# main.net
KiCad netlist of a schematic drawn in Altium Designer
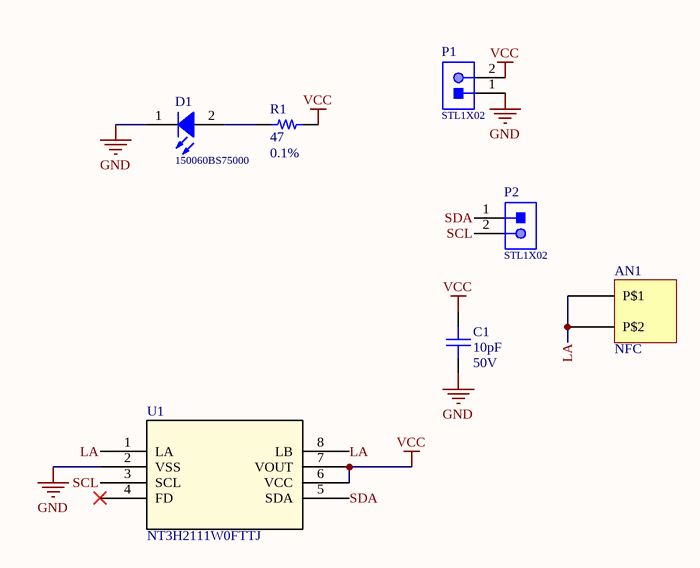
[diagram p0: main.SchDoc]

(export (version "E")
  (design (tool "Eeschema 10.0.6"))
  (components
    (comp (ref "AN1")
      (value "NFC")
      (footprint "NFC_Antenna")
      (libsource (lib "NFC_ANTENNA") (part "antenna"))
    )
    (comp (ref "C1")
      (value "10pF")
      (footprint "FP-CL10-IPC_A")
      (description "CAP, MLCC, C0G/NP0, 10PF, 50V,0603")
      (fields
        (field (name "VOLTAGE RATING") "50V")
        (field (name "TOLERANCE") "5%")
        (field (name "VOLTAGE") "50V")
      )
      (libsource (lib "ILH") (part "Capacitor Voltage Rating"))
    )
    (comp (ref "D1")
      (value "150060BS75000")
      (footprint "WL-SMCW_0603_H=0.7mm")
      (description "WL-SMCW SMT Mono-color Chip LED Waterclear, size 0603, Blue, 3.2V, 140deg")
      (fields (field (name "PUBLISHER") "Wurth Elektronik"))
      (libsource (lib "ILH") (part "Symbol"))
    )
    (comp (ref "P1")
      (value "STL1X02")
      (footprint "TSW-102-07-XXX-S")
      (description "Stiftleiste, 2-Pin")
      (libsource (lib "") (part "STL1X02_1"))
    )
    (comp (ref "P2")
      (value "STL1X02")
      (footprint "TSW-102-07-XXX-S")
      (description "Stiftleiste, 2-Pin")
      (libsource (lib "ILH") (part "STL1X02"))
    )
    (comp (ref "R1")
      (value "47")
      (footprint "RESC1608X06N 0603 Medium Density")
      (description "Thin Film Resistors - SMD 1/10W 47h Ohms 0.1% 0603 25ppm")
      (fields (field (name "TOLERANCE") "0.1%") (field (name "Comment") "RG1608P-470-B-T5"))
      (libsource (lib "ILH") (part "Resistor Tolerance"))
    )
    (comp (ref "U1")
      (value "NT3H2111W0FTTJ")
      (footprint "TSSOP_1W0FTTJ_NXP")
      (description "No Description Available")
      (libsource (lib "NT3H2111W0FTTJ") (part "NT3H2111W0FTTJ"))
    )
  )
  (nets
    (net (code "1") (name "/LA") (class "Default")
      (node (ref "AN1") (pin "P$1") (pinfunction "P$1_P$1") (pintype "passive"))
      (node (ref "AN1") (pin "P$2") (pinfunction "P$2_P$2") (pintype "passive"))
      (node (ref "U1") (pin "1") (pinfunction "LA_1") (pintype "passive"))
      (node (ref "U1") (pin "8") (pinfunction "LB_8") (pintype "passive"))
    )
    (net (code "2") (name "/SCL") (class "Default")
      (node (ref "P2") (pin "2") (pinfunction "2_2") (pintype "passive"))
      (node (ref "U1") (pin "3") (pinfunction "SCL_3") (pintype "passive"))
    )
    (net (code "3") (name "/SDA") (class "Default")
      (node (ref "P2") (pin "1") (pinfunction "1_1") (pintype "passive"))
      (node (ref "U1") (pin "5") (pinfunction "SDA_5") (pintype "passive"))
    )
    (net (code "4") (name "GND") (class "Default")
      (node (ref "C1") (pin "1") (pinfunction "1_1") (pintype "passive"))
      (node (ref "D1") (pin "1") (pinfunction "K_1") (pintype "passive"))
      (node (ref "P1") (pin "1") (pinfunction "1_1") (pintype "passive"))
      (node (ref "U1") (pin "2") (pinfunction "VSS_2") (pintype "power_in"))
    )
    (net (code "5") (name "Net-(D1-A)") (class "Default")
      (node (ref "D1") (pin "2") (pinfunction "A_2") (pintype "passive"))
      (node (ref "R1") (pin "1") (pinfunction "1_1") (pintype "passive"))
    )
    (net (code "6") (name "VCC") (class "Default")
      (node (ref "C1") (pin "2") (pinfunction "2_2") (pintype "passive"))
      (node (ref "P1") (pin "2") (pinfunction "2_2") (pintype "passive"))
      (node (ref "R1") (pin "2") (pinfunction "2_2") (pintype "passive"))
      (node (ref "U1") (pin "6") (pinfunction "VCC_6") (pintype "power_in"))
      (node (ref "U1") (pin "7") (pinfunction "VOUT_7") (pintype "passive"))
    )
    (net (code "7") (name "unconnected-(U1-FD-Pad4)") (class "Default")
      (node (ref "U1") (pin "4") (pinfunction "FD_4") (pintype "passive+no_connect"))
    )
  )
)
